# Clyde_main_board.net
KiCad netlist of a schematic drawn in EAGLE
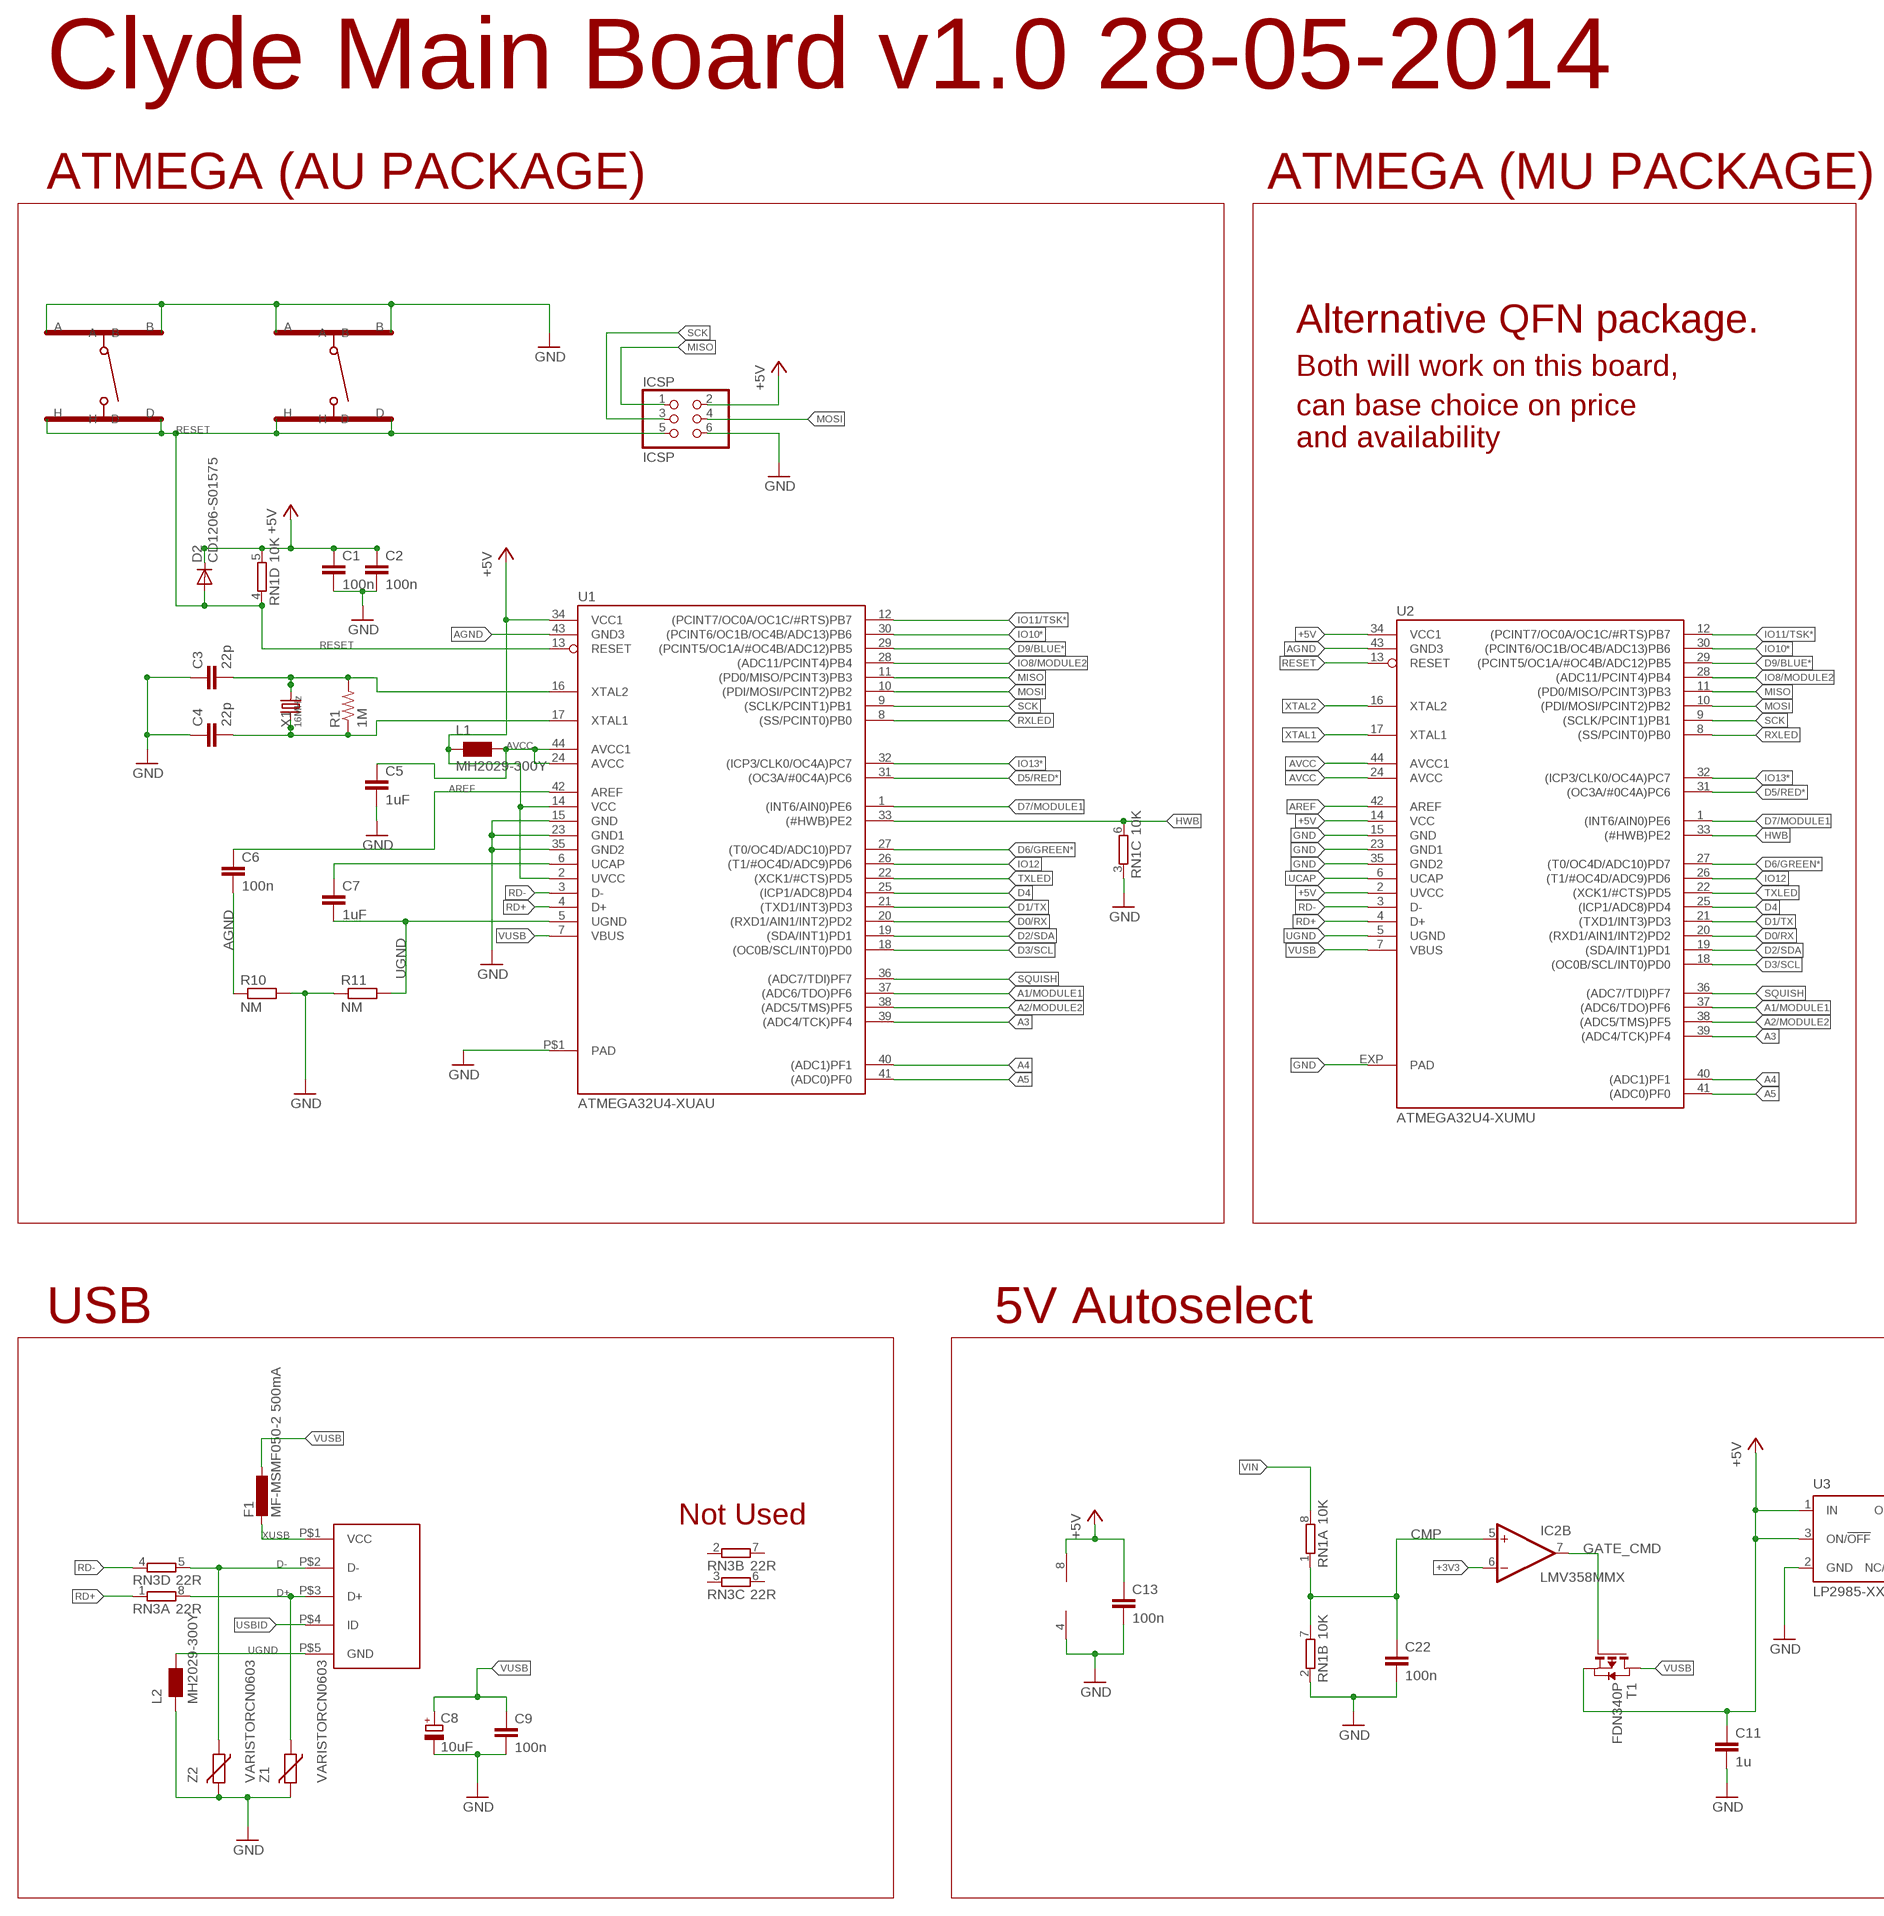
[diagram p0: schematic, sheet 1, part 1 of 2]
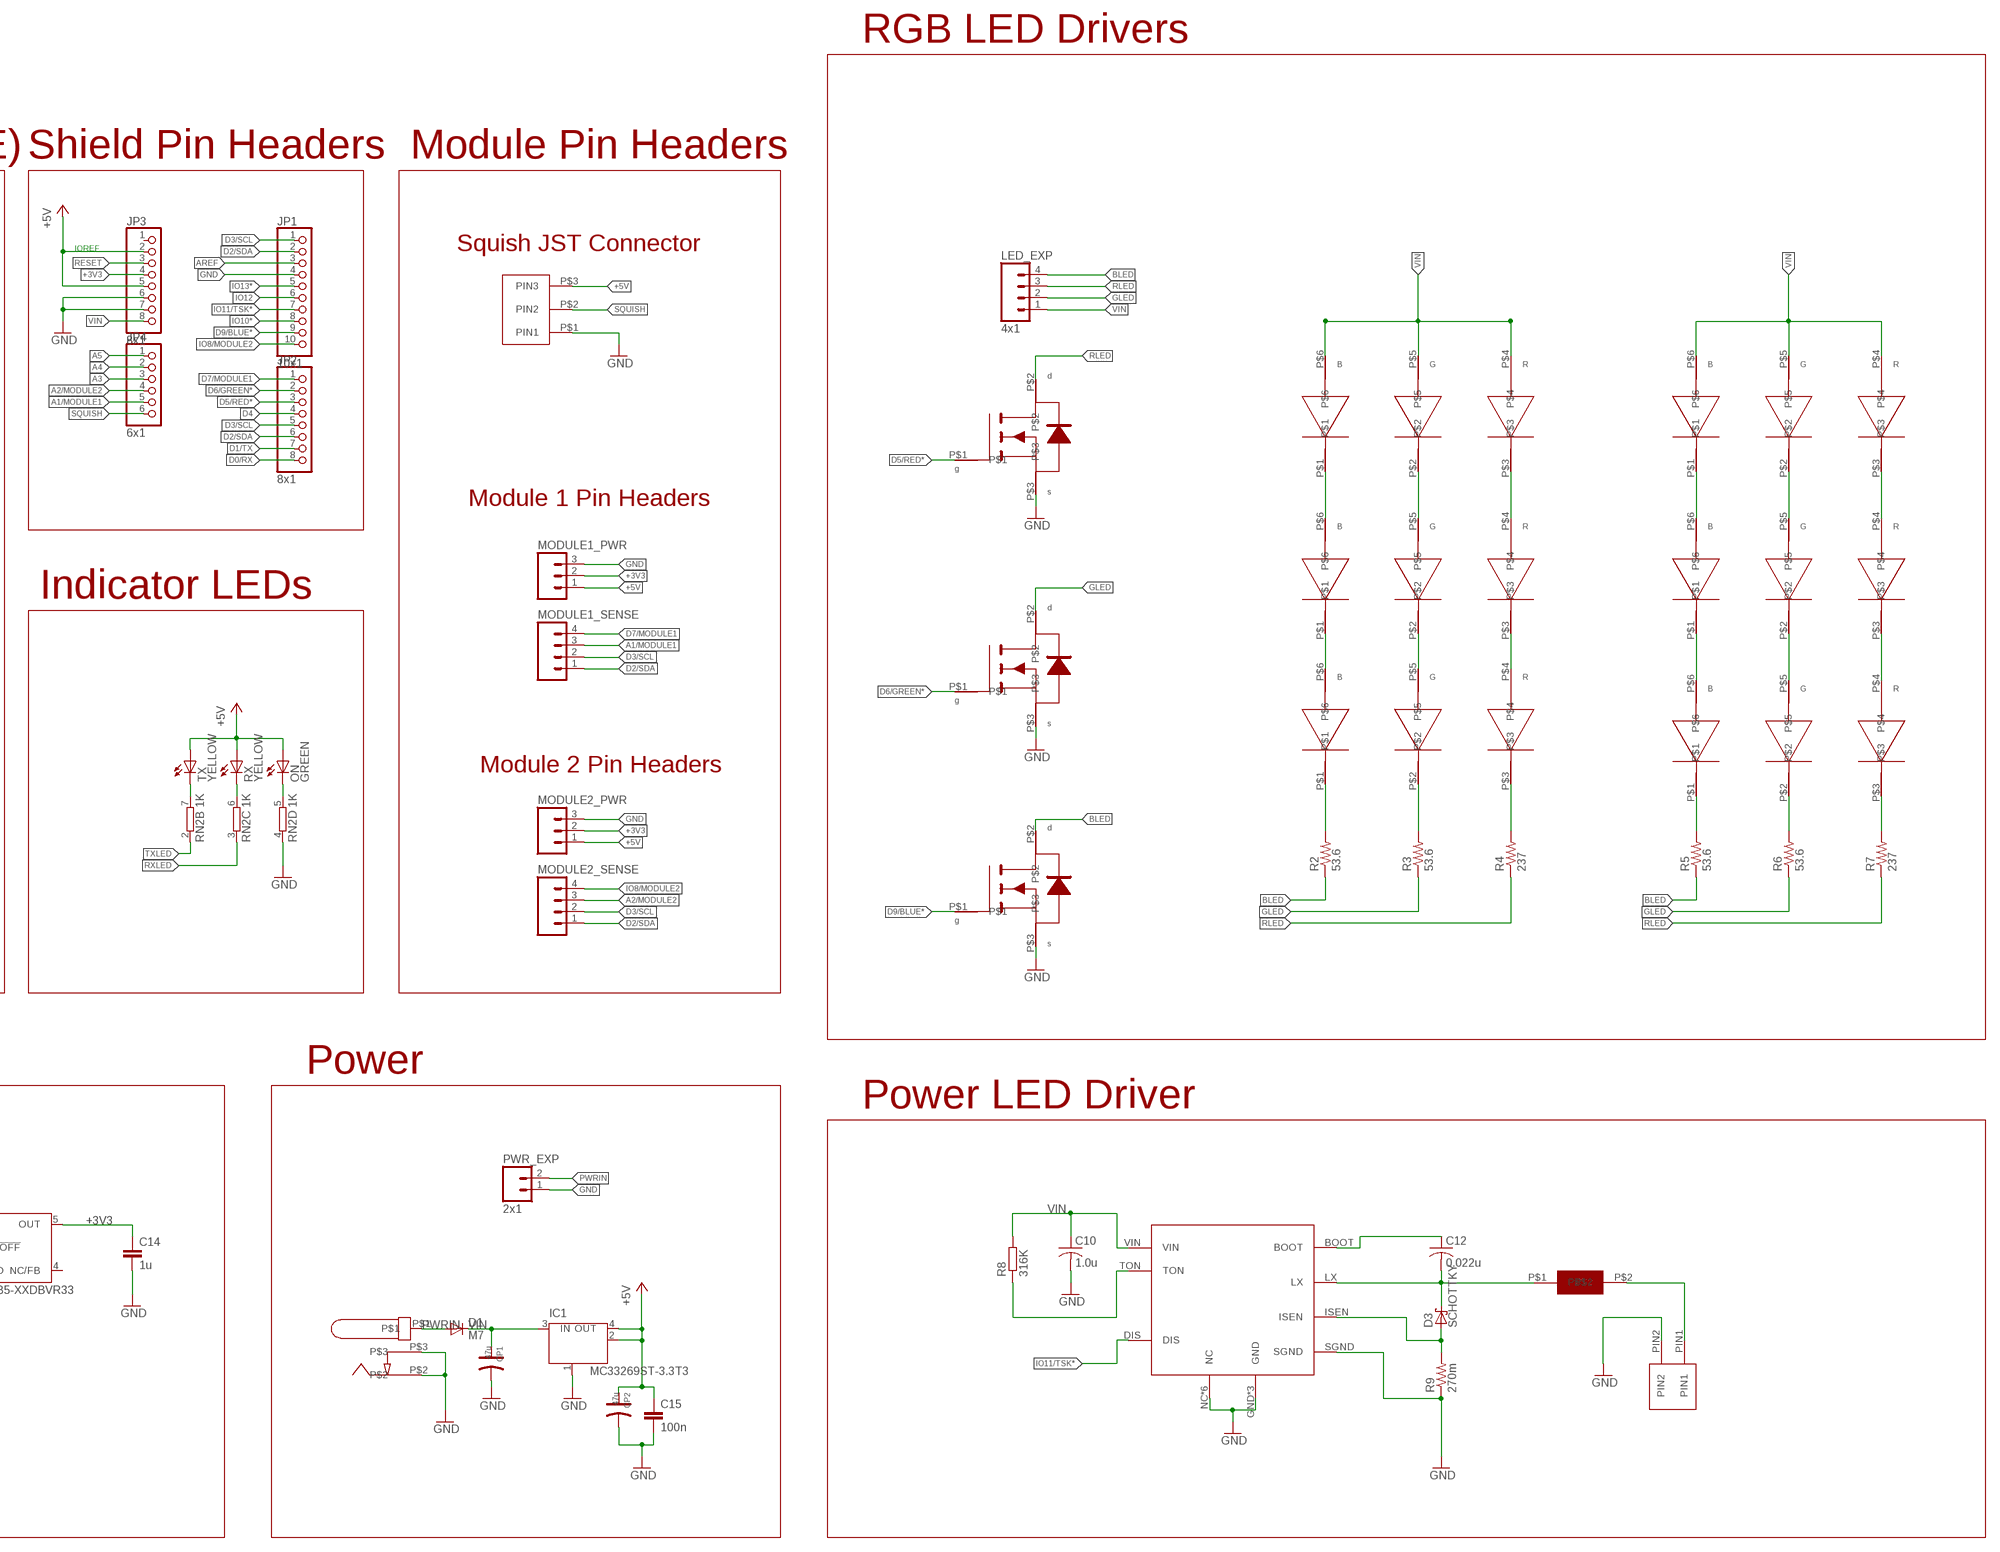
[diagram p1: schematic, sheet 1, part 2 of 2]

(export (version "E")
  (design (tool "Eeschema 10.0.6"))
  (components
    (comp (ref "2PIN_CONN")
      (value "XH_JST_CONN_2POS_TOP")
      (footprint "eagle-import:XH_JST_CONN_2POS_TOP")
      (libsource (lib "eagle-import") (part "XH_JST_CONN_2POS_TOP"))
    )
    (comp (ref "C1")
      (value "100n")
      (footprint "eagle-import:C0603-ROUND")
      (libsource (lib "eagle-import") (part "C-EUC0603"))
    )
    (comp (ref "C2")
      (value "100n")
      (footprint "eagle-import:C0603-ROUND")
      (libsource (lib "eagle-import") (part "C-EUC0603"))
    )
    (comp (ref "C3")
      (value "22p")
      (footprint "eagle-import:C0603-ROUND")
      (libsource (lib "eagle-import") (part "C-EUC0603"))
    )
    (comp (ref "C4")
      (value "22p")
      (footprint "eagle-import:C0603-ROUND")
      (libsource (lib "eagle-import") (part "C-EUC0603"))
    )
    (comp (ref "C5")
      (value "1uF")
      (footprint "eagle-import:C0603-ROUND")
      (libsource (lib "eagle-import") (part "C-EUC0603"))
    )
    (comp (ref "C6")
      (value "100n")
      (footprint "eagle-import:C0603-ROUND")
      (libsource (lib "eagle-import") (part "C-EUC0603"))
    )
    (comp (ref "C7")
      (value "1uF")
      (footprint "eagle-import:C0603-ROUND")
      (libsource (lib "eagle-import") (part "C-EUC0603"))
    )
    (comp (ref "C8")
      (value "10uF")
      (footprint "eagle-import:SMC_B")
      (libsource (lib "eagle-import") (part "CPOL-EUSMCB"))
    )
    (comp (ref "C9")
      (value "100n")
      (footprint "eagle-import:C0603-ROUND")
      (libsource (lib "eagle-import") (part "C-EUC0603"))
    )
    (comp (ref "C10")
      (value "1.0u")
      (footprint "eagle-import:C1210")
      (libsource (lib "eagle-import") (part "C-USC1210"))
    )
    (comp (ref "C11")
      (value "1u")
      (footprint "eagle-import:C0603-ROUND")
      (libsource (lib "eagle-import") (part "C-EUC0603"))
    )
    (comp (ref "C12")
      (value "0.022u")
      (footprint "eagle-import:C0805")
      (libsource (lib "eagle-import") (part "C-USC0805"))
    )
    (comp (ref "C13")
      (value "100n")
      (footprint "eagle-import:C0603-ROUND")
      (libsource (lib "eagle-import") (part "C-EUC0603"))
    )
    (comp (ref "C14")
      (value "1u")
      (footprint "eagle-import:C0603-ROUND")
      (libsource (lib "eagle-import") (part "C-EUC0603"))
    )
    (comp (ref "C15")
      (value "100n")
      (footprint "eagle-import:C0603-ROUND")
      (libsource (lib "eagle-import") (part "C-EUC0603"))
    )
    (comp (ref "C22")
      (value "100n")
      (footprint "eagle-import:C0603-ROUND")
      (libsource (lib "eagle-import") (part "C-EUC0603"))
    )
    (comp (ref "CP1")
      (value "47u")
      (footprint "eagle-import:ELECTRO-SMD-C-6MM")
      (libsource (lib "eagle-import") (part "CAP-ELECTRO-C"))
    )
    (comp (ref "CP2")
      (value "47u")
      (footprint "eagle-import:ELECTRO-SMD-C-6MM")
      (libsource (lib "eagle-import") (part "CAP-ELECTRO-C"))
    )
    (comp (ref "D1")
      (value "M7")
      (footprint "eagle-import:SMB")
      (libsource (lib "eagle-import") (part "DIODE-SMB"))
    )
    (comp (ref "D2")
      (value "CD1206-S01575")
      (footprint "eagle-import:MINIMELF")
      (libsource (lib "eagle-import") (part "DIODE-MINIMELF"))
    )
    (comp (ref "D3")
      (value "SCHOTTKY")
      (footprint "eagle-import:SMB")
      (libsource (lib "eagle-import") (part "SCHOTTKY-DIODESMD"))
    )
    (comp (ref "F1")
      (value "MF-MSMF050-2 500mA")
      (footprint "eagle-import:L1812")
      (libsource (lib "eagle-import") (part "L-EUL1812"))
    )
    (comp (ref "IC1")
      (value "MC33269ST-3.3T3")
      (footprint "eagle-import:SOT223")
      (libsource (lib "eagle-import") (part "MC33269ST-3.3T3"))
    )
    (comp (ref "IC2")
      (value "LMV358MMX")
      (footprint "eagle-import:MSOP08")
      (libsource (lib "eagle-import") (part "LMV358?MMX"))
    )
    (comp (ref "ICSP")
      (value "ICSP")
      (footprint "eagle-import:2X03")
      (libsource (lib "eagle-import") (part "PINHD-2X3"))
    )
    (comp (ref "IR_CONNECT")
      (value "XH_JST_CONN_3POS_SIDE_SMT")
      (footprint "eagle-import:XH_JST_CONN_3POS_SIDE_SMT")
      (libsource (lib "eagle-import") (part "XH_JST_CONN_3POS_SIDE_SMT"))
    )
    (comp (ref "I_LEDDRIVER")
      (value "TAIYO_YUDEN_6045_INDUCTOR")
      (footprint "eagle-import:TAIYO_YUDEN_6045_INDUCTOR")
      (libsource (lib "eagle-import") (part "TAIYO_YUDEN_6045_INDUCTOR"))
    )
    (comp (ref "J1")
      (value "MOLEX_VERT_MINIUSB")
      (footprint "eagle-import:MOLEX_VERT_MINIUSB")
      (libsource (lib "eagle-import") (part "MOLEX_VERT_MINIUSB"))
    )
    (comp (ref "JP1")
      (value "10x1")
      (footprint "eagle-import:1X10")
      (libsource (lib "eagle-import") (part "PINHD-1X10"))
    )
    (comp (ref "JP2")
      (value "8x1")
      (footprint "eagle-import:1X08")
      (libsource (lib "eagle-import") (part "PINHD-1X8"))
    )
    (comp (ref "JP3")
      (value "8x1")
      (footprint "eagle-import:1X08")
      (libsource (lib "eagle-import") (part "PINHD-1X8"))
    )
    (comp (ref "JP4")
      (value "6x1")
      (footprint "eagle-import:1X06")
      (libsource (lib "eagle-import") (part "PINHD-1X6"))
    )
    (comp (ref "L1")
      (value "MH2029-300Y")
      (footprint "eagle-import:0805")
      (libsource (lib "eagle-import") (part "WE-CBF_0805"))
    )
    (comp (ref "L2")
      (value "MH2029-300Y")
      (footprint "eagle-import:0805")
      (libsource (lib "eagle-import") (part "WE-CBF_0805"))
    )
    (comp (ref "LED_EXP")
      (value "4x1")
      (footprint "eagle-import:1X04_LONGPADS")
      (libsource (lib "eagle-import") (part "M04LONGPADS"))
    )
    (comp (ref "MODULE1_PWR")
      (value "M03PTH")
      (footprint "eagle-import:1X03")
      (libsource (lib "eagle-import") (part "M03PTH"))
    )
    (comp (ref "MODULE1_SENSE")
      (value "M04PTH")
      (footprint "eagle-import:1X04")
      (libsource (lib "eagle-import") (part "M04PTH"))
    )
    (comp (ref "MODULE2_PWR")
      (value "M03PTH")
      (footprint "eagle-import:1X03")
      (libsource (lib "eagle-import") (part "M03PTH"))
    )
    (comp (ref "MODULE2_SENSE")
      (value "M04PTH")
      (footprint "eagle-import:1X04")
      (libsource (lib "eagle-import") (part "M04PTH"))
    )
    (comp (ref "ON")
      (value "GREEN")
      (footprint "eagle-import:CHIPLED_0603")
      (libsource (lib "eagle-import") (part "LEDCHIPLED_0603"))
    )
    (comp (ref "PWR_EXP")
      (value "2x1")
      (footprint "eagle-import:SCREWTERMINAL-3.5MM-2")
      (libsource (lib "eagle-import") (part "M023.5MM"))
    )
    (comp (ref "PWR_JACK")
      (value "VERT_PWRJACK_PJ-006A_CUIINC")
      (footprint "eagle-import:VERT_PWRJACK_PJ-006A_CUIINC")
      (libsource (lib "eagle-import") (part "VERT_PWRJACK_PJ-006A_CUIINC"))
    )
    (comp (ref "R1")
      (value "1M")
      (footprint "eagle-import:0805")
      (libsource (lib "eagle-import") (part "RESISTOR0805-RES"))
    )
    (comp (ref "R2")
      (value "53.6")
      (footprint "eagle-import:R0603")
      (libsource (lib "eagle-import") (part "R-US_R0603"))
    )
    (comp (ref "R3")
      (value "53.6")
      (footprint "eagle-import:R0603")
      (libsource (lib "eagle-import") (part "R-US_R0603"))
    )
    (comp (ref "R4")
      (value "237")
      (footprint "eagle-import:R0603")
      (libsource (lib "eagle-import") (part "R-US_R0603"))
    )
    (comp (ref "R5")
      (value "53.6")
      (footprint "eagle-import:R0603")
      (libsource (lib "eagle-import") (part "R-US_R0603"))
    )
    (comp (ref "R6")
      (value "53.6")
      (footprint "eagle-import:R0603")
      (libsource (lib "eagle-import") (part "R-US_R0603"))
    )
    (comp (ref "R7")
      (value "237")
      (footprint "eagle-import:R0603")
      (libsource (lib "eagle-import") (part "R-US_R0603"))
    )
    (comp (ref "R8")
      (value "316K")
      (footprint "eagle-import:R0603-ROUND")
      (libsource (lib "eagle-import") (part "R-EU_R0603"))
    )
    (comp (ref "R9")
      (value "270m")
      (footprint "eagle-import:R0805")
      (libsource (lib "eagle-import") (part "resistor_R-US_R0805"))
    )
    (comp (ref "R10")
      (value "NM")
      (footprint "eagle-import:R0402_NM")
      (libsource (lib "eagle-import") (part "R_0402_NM"))
    )
    (comp (ref "R11")
      (value "NM")
      (footprint "eagle-import:R0402_NM")
      (libsource (lib "eagle-import") (part "R_0402_NM"))
    )
    (comp (ref "RGB1")
      (value "HANGZHOU_MULTICOLOR_3535WSA")
      (footprint "eagle-import:HANGZHOU_MULTCOLOR_3535WSZ")
      (libsource (lib "eagle-import") (part "HANGZHOU_MULTICOLOR_3535WSA"))
    )
    (comp (ref "RGB2")
      (value "HANGZHOU_MULTICOLOR_3535WSA")
      (footprint "eagle-import:HANGZHOU_MULTCOLOR_3535WSZ")
      (libsource (lib "eagle-import") (part "HANGZHOU_MULTICOLOR_3535WSA"))
    )
    (comp (ref "RGB3")
      (value "HANGZHOU_MULTICOLOR_3535WSA")
      (footprint "eagle-import:HANGZHOU_MULTCOLOR_3535WSZ")
      (libsource (lib "eagle-import") (part "HANGZHOU_MULTICOLOR_3535WSA"))
    )
    (comp (ref "RGB4")
      (value "HANGZHOU_MULTICOLOR_3535WSA")
      (footprint "eagle-import:HANGZHOU_MULTCOLOR_3535WSZ")
      (libsource (lib "eagle-import") (part "HANGZHOU_MULTICOLOR_3535WSA"))
    )
    (comp (ref "RGB5")
      (value "HANGZHOU_MULTICOLOR_3535WSA")
      (footprint "eagle-import:HANGZHOU_MULTCOLOR_3535WSZ")
      (libsource (lib "eagle-import") (part "HANGZHOU_MULTICOLOR_3535WSA"))
    )
    (comp (ref "RGB6")
      (value "HANGZHOU_MULTICOLOR_3535WSA")
      (footprint "eagle-import:HANGZHOU_MULTCOLOR_3535WSZ")
      (libsource (lib "eagle-import") (part "HANGZHOU_MULTICOLOR_3535WSA"))
    )
    (comp (ref "RN1")
      (value "10K")
      (footprint "eagle-import:CAY16")
      (libsource (lib "eagle-import") (part "4R-NCAY16"))
    )
    (comp (ref "RN2")
      (value "1K")
      (footprint "eagle-import:CAY16")
      (libsource (lib "eagle-import") (part "4R-NCAY16"))
    )
    (comp (ref "RN3")
      (value "22R")
      (footprint "eagle-import:CAY16")
      (libsource (lib "eagle-import") (part "4R-NCAY16"))
    )
    (comp (ref "RST")
      (value "COMAX_MINISWITCH")
      (footprint "eagle-import:COMAX_MINISWITCH")
      (libsource (lib "eagle-import") (part "COMAX_MINISWITCH"))
    )
    (comp (ref "RST1")
      (value "COMAX_MINISWITCH")
      (footprint "eagle-import:COMAX_MINISWITCH")
      (libsource (lib "eagle-import") (part "COMAX_MINISWITCH"))
    )
    (comp (ref "RX")
      (value "YELLOW")
      (footprint "eagle-import:CHIPLED_0603")
      (libsource (lib "eagle-import") (part "LEDCHIPLED_0603"))
    )
    (comp (ref "T1")
      (value "FDN340P")
      (footprint "eagle-import:SOT-23")
      (libsource (lib "eagle-import") (part "PMOSSOT23"))
    )
    (comp (ref "TBLUE")
      (value "SI2302DS_MOSFET")
      (footprint "eagle-import:SI2302DS_MOSFET")
      (libsource (lib "eagle-import") (part "SI2302DS_MOSFET"))
    )
    (comp (ref "TGREEN")
      (value "SI2302DS_MOSFET")
      (footprint "eagle-import:SI2302DS_MOSFET")
      (libsource (lib "eagle-import") (part "SI2302DS_MOSFET"))
    )
    (comp (ref "TRED")
      (value "SI2302DS_MOSFET")
      (footprint "eagle-import:SI2302DS_MOSFET")
      (libsource (lib "eagle-import") (part "SI2302DS_MOSFET"))
    )
    (comp (ref "TX")
      (value "YELLOW")
      (footprint "eagle-import:CHIPLED_0603")
      (libsource (lib "eagle-import") (part "LEDCHIPLED_0603"))
    )
    (comp (ref "U1")
      (value "ATMEGA32U4-XUAU")
      (footprint "eagle-import:TQFP44-PAD")
      (libsource (lib "eagle-import") (part "ATMEGA32U4-XUAU"))
    )
    (comp (ref "U2")
      (value "ATMEGA32U4-XUMU")
      (footprint "eagle-import:QFN44ML7X7")
      (libsource (lib "eagle-import") (part "ATMEGA32U4-XUMU"))
    )
    (comp (ref "U3")
      (value "LP2985-XXDBVR33")
      (footprint "eagle-import:SOT23-DBV")
      (libsource (lib "eagle-import") (part "LP2985-XXDBVR33"))
    )
    (comp (ref "U4")
      (value "ALLEGRO_A6210")
      (footprint "eagle-import:ALLEGRO_A6210")
      (libsource (lib "eagle-import") (part "ALLEGRO_A6210"))
    )
    (comp (ref "X1")
      (value "16MHz")
      (footprint "eagle-import:XTAL_THRU_SMT")
      (libsource (lib "eagle-import") (part "XTAL_THRU_SMD"))
    )
    (comp (ref "Z1")
      (value "VARISTORCN0603")
      (footprint "eagle-import:CT_CN0603")
      (libsource (lib "eagle-import") (part "VARISTORCN0603"))
    )
    (comp (ref "Z2")
      (value "VARISTORCN0603")
      (footprint "eagle-import:CT_CN0603")
      (libsource (lib "eagle-import") (part "VARISTORCN0603"))
    )
  )
  (nets
    (net (code "1") (name "+3V3") (class "Default")
      (node (ref "C14") (pin "1") (pinfunction "1_1") (pintype "passive"))
      (node (ref "IC2") (pin "6") (pinfunction "-IN_6") (pintype "input"))
      (node (ref "JP3") (pin "4") (pinfunction "4_4") (pintype "passive"))
      (node (ref "MODULE1_PWR") (pin "2") (pinfunction "2_2") (pintype "passive"))
      (node (ref "MODULE2_PWR") (pin "2") (pinfunction "2_2") (pintype "passive"))
      (node (ref "U3") (pin "5") (pinfunction "OUT_5") (pintype "passive"))
    )
    (net (code "2") (name "+5V") (class "Default")
      (node (ref "C1") (pin "1") (pinfunction "1_1") (pintype "passive"))
      (node (ref "C11") (pin "1") (pinfunction "1_1") (pintype "passive"))
      (node (ref "C13") (pin "1") (pinfunction "1_1") (pintype "passive"))
      (node (ref "C15") (pin "1") (pinfunction "1_1") (pintype "passive"))
      (node (ref "C2") (pin "1") (pinfunction "1_1") (pintype "passive"))
      (node (ref "CP2") (pin "+") (pinfunction "+_+") (pintype "passive"))
      (node (ref "D2") (pin "C") (pinfunction "C_C") (pintype "passive"))
      (node (ref "IC1") (pin "2") (pinfunction "OUT_2") (pintype "passive"))
      (node (ref "IC1") (pin "4") (pinfunction "OUT_4") (pintype "passive"))
      (node (ref "IC2") (pin "8") (pinfunction "V+_8") (pintype "power_in"))
      (node (ref "ICSP") (pin "2") (pinfunction "2_2") (pintype "passive"))
      (node (ref "IR_CONNECT") (pin "P$3") (pinfunction "PIN3_P$3") (pintype "bidirectional"))
      (node (ref "JP3") (pin "2") (pinfunction "2_2") (pintype "passive"))
      (node (ref "JP3") (pin "5") (pinfunction "5_5") (pintype "passive"))
      (node (ref "L1") (pin "1") (pinfunction "1_1") (pintype "passive"))
      (node (ref "MODULE1_PWR") (pin "1") (pinfunction "1_1") (pintype "passive"))
      (node (ref "MODULE2_PWR") (pin "1") (pinfunction "1_1") (pintype "passive"))
      (node (ref "ON") (pin "A") (pinfunction "A_A") (pintype "passive"))
      (node (ref "RN1") (pin "5") (pinfunction "2_5") (pintype "passive"))
      (node (ref "RX") (pin "A") (pinfunction "A_A") (pintype "passive"))
      (node (ref "T1") (pin "2") (pinfunction "S_2") (pintype "passive"))
      (node (ref "TX") (pin "A") (pinfunction "A_A") (pintype "passive"))
      (node (ref "U1") (pin "14") (pinfunction "VCC_14") (pintype "power_in"))
      (node (ref "U1") (pin "2") (pinfunction "UVCC_2") (pintype "power_in"))
      (node (ref "U1") (pin "34") (pinfunction "VCC1_34") (pintype "power_in"))
      (node (ref "U2") (pin "14") (pinfunction "VCC_14") (pintype "power_in"))
      (node (ref "U2") (pin "2") (pinfunction "UVCC_2") (pintype "power_in"))
      (node (ref "U2") (pin "34") (pinfunction "VCC1_34") (pintype "power_in"))
      (node (ref "U3") (pin "1") (pinfunction "IN_1") (pintype "input"))
      (node (ref "U3") (pin "3") (pinfunction "ON/~{OFF}_3") (pintype "input"))
    )
    (net (code "3") (name "/CMP") (class "Default")
      (node (ref "C22") (pin "1") (pinfunction "1_1") (pintype "passive"))
      (node (ref "IC2") (pin "5") (pinfunction "+IN_5") (pintype "input"))
      (node (ref "RN1") (pin "1") (pinfunction "1_1") (pintype "passive"))
      (node (ref "RN1") (pin "7") (pinfunction "2_7") (pintype "passive"))
    )
    (net (code "4") (name "/D+") (class "Default")
      (node (ref "J1") (pin "P$3") (pinfunction "D+_P$3") (pintype "bidirectional"))
      (node (ref "RN3") (pin "8") (pinfunction "2_8") (pintype "passive"))
      (node (ref "Z1") (pin "1") (pinfunction "1_1") (pintype "passive"))
    )
    (net (code "5") (name "/D-") (class "Default")
      (node (ref "J1") (pin "P$2") (pinfunction "D-_P$2") (pintype "bidirectional"))
      (node (ref "RN3") (pin "5") (pinfunction "2_5") (pintype "passive"))
      (node (ref "Z2") (pin "1") (pinfunction "1_1") (pintype "passive"))
    )
    (net (code "6") (name "/GATE_CMD") (class "Default")
      (node (ref "IC2") (pin "7") (pinfunction "OUT_7") (pintype "output"))
      (node (ref "T1") (pin "3") (pinfunction "G_3") (pintype "passive"))
    )
    (net (code "7") (name "/XUSB") (class "Default")
      (node (ref "F1") (pin "2") (pinfunction "2_2") (pintype "passive"))
      (node (ref "J1") (pin "P$1") (pinfunction "VCC_P$1") (pintype "bidirectional"))
    )
    (net (code "8") (name "A1{slash}MODULE1") (class "Default")
      (node (ref "JP4") (pin "5") (pinfunction "5_5") (pintype "passive"))
      (node (ref "MODULE1_SENSE") (pin "3") (pinfunction "3_3") (pintype "passive"))
      (node (ref "U1") (pin "37") (pinfunction "(ADC6/TDO)PF6_37") (pintype "bidirectional"))
      (node (ref "U2") (pin "37") (pinfunction "(ADC6/TDO)PF6_37") (pintype "bidirectional"))
    )
    (net (code "9") (name "A2{slash}MODULE2") (class "Default")
      (node (ref "JP4") (pin "4") (pinfunction "4_4") (pintype "passive"))
      (node (ref "MODULE2_SENSE") (pin "3") (pinfunction "3_3") (pintype "passive"))
      (node (ref "U1") (pin "38") (pinfunction "(ADC5/TMS)PF5_38") (pintype "bidirectional"))
      (node (ref "U2") (pin "38") (pinfunction "(ADC5/TMS)PF5_38") (pintype "bidirectional"))
    )
    (net (code "10") (name "A3") (class "Default")
      (node (ref "JP4") (pin "3") (pinfunction "3_3") (pintype "passive"))
      (node (ref "U1") (pin "39") (pinfunction "(ADC4/TCK)PF4_39") (pintype "bidirectional"))
      (node (ref "U2") (pin "39") (pinfunction "(ADC4/TCK)PF4_39") (pintype "bidirectional"))
    )
    (net (code "11") (name "A4") (class "Default")
      (node (ref "JP4") (pin "2") (pinfunction "2_2") (pintype "passive"))
      (node (ref "U1") (pin "40") (pinfunction "(ADC1)PF1_40") (pintype "bidirectional"))
      (node (ref "U2") (pin "40") (pinfunction "(ADC1)PF1_40") (pintype "bidirectional"))
    )
    (net (code "12") (name "A5") (class "Default")
      (node (ref "JP4") (pin "1") (pinfunction "1_1") (pintype "passive"))
      (node (ref "U1") (pin "41") (pinfunction "(ADC0)PF0_41") (pintype "bidirectional"))
      (node (ref "U2") (pin "41") (pinfunction "(ADC0)PF0_41") (pintype "bidirectional"))
    )
    (net (code "13") (name "AGND") (class "Default")
      (node (ref "C6") (pin "2") (pinfunction "2_2") (pintype "passive"))
      (node (ref "R10") (pin "1") (pinfunction "1_1") (pintype "passive"))
      (node (ref "U1") (pin "43") (pinfunction "GND3_43") (pintype "power_in"))
      (node (ref "U2") (pin "43") (pinfunction "GND3_43") (pintype "power_in"))
    )
    (net (code "14") (name "AREF") (class "Default")
      (node (ref "C6") (pin "1") (pinfunction "1_1") (pintype "passive"))
      (node (ref "JP1") (pin "3") (pinfunction "3_3") (pintype "passive"))
      (node (ref "U1") (pin "42") (pinfunction "AREF_42") (pintype "power_in"))
      (node (ref "U2") (pin "42") (pinfunction "AREF_42") (pintype "power_in"))
    )
    (net (code "15") (name "AVCC") (class "Default")
      (node (ref "C5") (pin "1") (pinfunction "1_1") (pintype "passive"))
      (node (ref "L1") (pin "2") (pinfunction "2_2") (pintype "passive"))
      (node (ref "U1") (pin "24") (pinfunction "AVCC_24") (pintype "power_in"))
      (node (ref "U1") (pin "44") (pinfunction "AVCC1_44") (pintype "power_in"))
      (node (ref "U2") (pin "24") (pinfunction "AVCC_24") (pintype "power_in"))
      (node (ref "U2") (pin "44") (pinfunction "AVCC1_44") (pintype "power_in"))
    )
    (net (code "16") (name "BLED") (class "Default")
      (node (ref "LED_EXP") (pin "4") (pinfunction "4_4") (pintype "passive"))
      (node (ref "R2") (pin "1") (pinfunction "1_1") (pintype "passive"))
      (node (ref "R5") (pin "1") (pinfunction "1_1") (pintype "passive"))
      (node (ref "TBLUE") (pin "P$2") (pinfunction "P$2_P$2") (pintype "bidirectional"))
    )
    (net (code "17") (name "D0{slash}RX") (class "Default")
      (node (ref "JP2") (pin "8") (pinfunction "8_8") (pintype "passive"))
      (node (ref "U1") (pin "20") (pinfunction "(RXD1/AIN1/INT2)PD2_20") (pintype "bidirectional"))
      (node (ref "U2") (pin "20") (pinfunction "(RXD1/AIN1/INT2)PD2_20") (pintype "bidirectional"))
    )
    (net (code "18") (name "D1{slash}TX") (class "Default")
      (node (ref "JP2") (pin "7") (pinfunction "7_7") (pintype "passive"))
      (node (ref "U1") (pin "21") (pinfunction "(TXD1/INT3)PD3_21") (pintype "bidirectional"))
      (node (ref "U2") (pin "21") (pinfunction "(TXD1/INT3)PD3_21") (pintype "bidirectional"))
    )
    (net (code "19") (name "D2{slash}SDA") (class "Default")
      (node (ref "JP1") (pin "2") (pinfunction "2_2") (pintype "passive"))
      (node (ref "JP2") (pin "6") (pinfunction "6_6") (pintype "passive"))
      (node (ref "MODULE1_SENSE") (pin "1") (pinfunction "1_1") (pintype "passive"))
      (node (ref "MODULE2_SENSE") (pin "1") (pinfunction "1_1") (pintype "passive"))
      (node (ref "U1") (pin "19") (pinfunction "(SDA/INT1)PD1_19") (pintype "bidirectional"))
      (node (ref "U2") (pin "19") (pinfunction "(SDA/INT1)PD1_19") (pintype "bidirectional"))
    )
    (net (code "20") (name "D3{slash}SCL") (class "Default")
      (node (ref "JP1") (pin "1") (pinfunction "1_1") (pintype "passive"))
      (node (ref "JP2") (pin "5") (pinfunction "5_5") (pintype "passive"))
      (node (ref "MODULE1_SENSE") (pin "2") (pinfunction "2_2") (pintype "passive"))
      (node (ref "MODULE2_SENSE") (pin "2") (pinfunction "2_2") (pintype "passive"))
      (node (ref "U1") (pin "18") (pinfunction "(OC0B/SCL/INT0)PD0_18") (pintype "bidirectional"))
      (node (ref "U2") (pin "18") (pinfunction "(OC0B/SCL/INT0)PD0_18") (pintype "bidirectional"))
    )
    (net (code "21") (name "D4") (class "Default")
      (node (ref "JP2") (pin "4") (pinfunction "4_4") (pintype "passive"))
      (node (ref "U1") (pin "25") (pinfunction "(ICP1/ADC8)PD4_25") (pintype "bidirectional"))
      (node (ref "U2") (pin "25") (pinfunction "(ICP1/ADC8)PD4_25") (pintype "bidirectional"))
    )
    (net (code "22") (name "D5{slash}RED*") (class "Default")
      (node (ref "JP2") (pin "3") (pinfunction "3_3") (pintype "passive"))
      (node (ref "TRED") (pin "P$1") (pinfunction "P$1_P$1") (pintype "bidirectional"))
      (node (ref "U1") (pin "31") (pinfunction "(OC3A/#0C4A)PC6_31") (pintype "bidirectional"))
      (node (ref "U2") (pin "31") (pinfunction "(OC3A/#0C4A)PC6_31") (pintype "bidirectional"))
    )
    (net (code "23") (name "D6{slash}GREEN*") (class "Default")
      (node (ref "JP2") (pin "2") (pinfunction "2_2") (pintype "passive"))
      (node (ref "TGREEN") (pin "P$1") (pinfunction "P$1_P$1") (pintype "bidirectional"))
      (node (ref "U1") (pin "27") (pinfunction "(T0/OC4D/ADC10)PD7_27") (pintype "bidirectional"))
      (node (ref "U2") (pin "27") (pinfunction "(T0/OC4D/ADC10)PD7_27") (pintype "bidirectional"))
    )
    (net (code "24") (name "D7{slash}MODULE1") (class "Default")
      (node (ref "JP2") (pin "1") (pinfunction "1_1") (pintype "passive"))
      (node (ref "MODULE1_SENSE") (pin "4") (pinfunction "4_4") (pintype "passive"))
      (node (ref "U1") (pin "1") (pinfunction "(INT6/AIN0)PE6_1") (pintype "bidirectional"))
      (node (ref "U2") (pin "1") (pinfunction "(INT6/AIN0)PE6_1") (pintype "bidirectional"))
    )
    (net (code "25") (name "D9{slash}BLUE*") (class "Default")
      (node (ref "JP1") (pin "9") (pinfunction "9_9") (pintype "passive"))
      (node (ref "TBLUE") (pin "P$1") (pinfunction "P$1_P$1") (pintype "bidirectional"))
      (node (ref "U1") (pin "29") (pinfunction "(PCINT5/OC1A/#OC4B/ADC12)PB5_29") (pintype "bidirectional"))
      (node (ref "U2") (pin "29") (pinfunction "(PCINT5/OC1A/#OC4B/ADC12)PB5_29") (pintype "bidirectional"))
    )
    (net (code "26") (name "GLED") (class "Default")
      (node (ref "LED_EXP") (pin "2") (pinfunction "2_2") (pintype "passive"))
      (node (ref "R3") (pin "1") (pinfunction "1_1") (pintype "passive"))
      (node (ref "R6") (pin "1") (pinfunction "1_1") (pintype "passive"))
      (node (ref "TGREEN") (pin "P$2") (pinfunction "P$2_P$2") (pintype "bidirectional"))
    )
    (net (code "27") (name "GND") (class "Default")
      (node (ref "2PIN_CONN") (pin "PIN2") (pinfunction "PIN2_PIN2") (pintype "bidirectional"))
      (node (ref "C1") (pin "2") (pinfunction "2_2") (pintype "passive"))
      (node (ref "C10") (pin "2") (pinfunction "2_2") (pintype "passive"))
      (node (ref "C11") (pin "2") (pinfunction "2_2") (pintype "passive"))
      (node (ref "C13") (pin "2") (pinfunction "2_2") (pintype "passive"))
      (node (ref "C14") (pin "2") (pinfunction "2_2") (pintype "passive"))
      (node (ref "C15") (pin "2") (pinfunction "2_2") (pintype "passive"))
      (node (ref "C2") (pin "2") (pinfunction "2_2") (pintype "passive"))
      (node (ref "C22") (pin "2") (pinfunction "2_2") (pintype "passive"))
      (node (ref "C3") (pin "1") (pinfunction "1_1") (pintype "passive"))
      (node (ref "C4") (pin "1") (pinfunction "1_1") (pintype "passive"))
      (node (ref "C5") (pin "2") (pinfunction "2_2") (pintype "passive"))
      (node (ref "C8") (pin "-") (pinfunction "-_-") (pintype "passive"))
      (node (ref "C9") (pin "2") (pinfunction "2_2") (pintype "passive"))
      (node (ref "CP1") (pin "-") (pinfunction "-_-") (pintype "passive"))
      (node (ref "CP2") (pin "-") (pinfunction "-_-") (pintype "passive"))
      (node (ref "IC1") (pin "1") (pinfunction "GND/ADJ_1") (pintype "input"))
      (node (ref "IC2") (pin "4") (pinfunction "V-_4") (pintype "power_in"))
      (node (ref "ICSP") (pin "6") (pinfunction "6_6") (pintype "passive"))
      (node (ref "IR_CONNECT") (pin "P$1") (pinfunction "PIN1_P$1") (pintype "bidirectional"))
      (node (ref "JP1") (pin "4") (pinfunction "4_4") (pintype "passive"))
      (node (ref "JP3") (pin "6") (pinfunction "6_6") (pintype "passive"))
      (node (ref "JP3") (pin "7") (pinfunction "7_7") (pintype "passive"))
      (node (ref "L2") (pin "1") (pinfunction "1_1") (pintype "passive"))
      (node (ref "MODULE1_PWR") (pin "3") (pinfunction "3_3") (pintype "passive"))
      (node (ref "MODULE2_PWR") (pin "3") (pinfunction "3_3") (pintype "passive"))
      (node (ref "PWR_EXP") (pin "1") (pinfunction "1_1") (pintype "passive"))
      (node (ref "PWR_JACK") (pin "P$2") (pinfunction "P$2_P$2") (pintype "bidirectional"))
      (node (ref "PWR_JACK") (pin "P$3") (pinfunction "P$3_P$3") (pintype "bidirectional"))
      (node (ref "R10") (pin "2") (pinfunction "2_2") (pintype "passive"))
      (node (ref "R11") (pin "1") (pinfunction "1_1") (pintype "passive"))
      (node (ref "R9") (pin "1") (pinfunction "1_1") (pintype "passive"))
      (node (ref "RN1") (pin "2") (pinfunction "1_2") (pintype "passive"))
      (node (ref "RN1") (pin "3") (pinfunction "1_3") (pintype "passive"))
      (node (ref "RN2") (pin "4") (pinfunction "1_4") (pintype "passive"))
      (node (ref "RST") (pin "A") (pinfunction "A_A") (pintype "bidirectional"))
      (node (ref "RST") (pin "B") (pinfunction "B_B") (pintype "bidirectional"))
      (node (ref "RST1") (pin "A") (pinfunction "A_A") (pintype "bidirectional"))
      (node (ref "RST1") (pin "B") (pinfunction "B_B") (pintype "bidirectional"))
      (node (ref "TBLUE") (pin "P$3") (pinfunction "P$3_P$3") (pintype "bidirectional"))
      (node (ref "TGREEN") (pin "P$3") (pinfunction "P$3_P$3") (pintype "bidirectional"))
      (node (ref "TRED") (pin "P$3") (pinfunction "P$3_P$3") (pintype "bidirectional"))
      (node (ref "U1") (pin "15") (pinfunction "GND_15") (pintype "power_in"))
      (node (ref "U1") (pin "23") (pinfunction "GND1_23") (pintype "power_in"))
      (node (ref "U1") (pin "35") (pinfunction "GND2_35") (pintype "power_in"))
      (node (ref "U1") (pin "P$1") (pinfunction "PAD_P$1") (pintype "power_in"))
      (node (ref "U2") (pin "15") (pinfunction "GND_15") (pintype "power_in"))
      (node (ref "U2") (pin "23") (pinfunction "GND1_23") (pintype "power_in"))
      (node (ref "U2") (pin "35") (pinfunction "GND2_35") (pintype "power_in"))
      (node (ref "U2") (pin "EXP") (pinfunction "PAD_EXP") (pintype "power_in"))
      (node (ref "U3") (pin "2") (pinfunction "GND_2") (pintype "power_in"))
      (node (ref "U4") (pin "GND") (pinfunction "GND_GND") (pintype "bidirectional"))
      (node (ref "U4") (pin "GND1") (pinfunction "GND_GND1") (pintype "bidirectional"))
      (node (ref "U4") (pin "GND2") (pinfunction "GND_GND2") (pintype "bidirectional"))
      (node (ref "U4") (pin "NC") (pinfunction "NC_NC") (pintype "bidirectional"))
      (node (ref "U4") (pin "NC1") (pinfunction "NC_NC1") (pintype "bidirectional"))
      (node (ref "U4") (pin "NC2") (pinfunction "NC_NC2") (pintype "bidirectional"))
      (node (ref "U4") (pin "NC3") (pinfunction "NC_NC3") (pintype "bidirectional"))
      (node (ref "U4") (pin "NC4") (pinfunction "NC_NC4") (pintype "bidirectional"))
      (node (ref "U4") (pin "NC5") (pinfunction "NC_NC5") (pintype "bidirectional"))
      (node (ref "U4") (pin "SGND") (pinfunction "SGND_SGND") (pintype "bidirectional"))
      (node (ref "Z1") (pin "2") (pinfunction "2_2") (pintype "passive"))
      (node (ref "Z2") (pin "2") (pinfunction "2_2") (pintype "passive"))
    )
    (net (code "28") (name "HWB") (class "Default")
      (node (ref "RN1") (pin "6") (pinfunction "2_6") (pintype "passive"))
      (node (ref "U1") (pin "33") (pinfunction "(#HWB)PE2_33") (pintype "bidirectional"))
      (node (ref "U2") (pin "33") (pinfunction "(#HWB)PE2_33") (pintype "bidirectional"))
    )
    (net (code "29") (name "IO8{slash}MODULE2") (class "Default")
      (node (ref "JP1") (pin "10") (pinfunction "10_10") (pintype "passive"))
      (node (ref "MODULE2_SENSE") (pin "4") (pinfunction "4_4") (pintype "passive"))
      (node (ref "U1") (pin "28") (pinfunction "(ADC11/PCINT4)PB4_28") (pintype "bidirectional"))
      (node (ref "U2") (pin "28") (pinfunction "(ADC11/PCINT4)PB4_28") (pintype "bidirectional"))
    )
    (net (code "30") (name "IO10*") (class "Default")
      (node (ref "JP1") (pin "8") (pinfunction "8_8") (pintype "passive"))
      (node (ref "U1") (pin "30") (pinfunction "(PCINT6/OC1B/OC4B/ADC13)PB6_30") (pintype "bidirectional"))
      (node (ref "U2") (pin "30") (pinfunction "(PCINT6/OC1B/OC4B/ADC13)PB6_30") (pintype "bidirectional"))
    )
    (net (code "31") (name "IO11{slash}TSK*") (class "Default")
      (node (ref "JP1") (pin "7") (pinfunction "7_7") (pintype "passive"))
      (node (ref "U1") (pin "12") (pinfunction "(PCINT7/OC0A/OC1C/#RTS)PB7_12") (pintype "bidirectional"))
      (node (ref "U2") (pin "12") (pinfunction "(PCINT7/OC0A/OC1C/#RTS)PB7_12") (pintype "bidirectional"))
      (node (ref "U4") (pin "DIS") (pinfunction "DIS_DIS") (pintype "bidirectional"))
    )
    (net (code "32") (name "IO12") (class "Default")
      (node (ref "JP1") (pin "6") (pinfunction "6_6") (pintype "passive"))
      (node (ref "U1") (pin "26") (pinfunction "(T1/#OC4D/ADC9)PD6_26") (pintype "bidirectional"))
      (node (ref "U2") (pin "26") (pinfunction "(T1/#OC4D/ADC9)PD6_26") (pintype "bidirectional"))
    )
    (net (code "33") (name "IO13*") (class "Default")
      (node (ref "JP1") (pin "5") (pinfunction "5_5") (pintype "passive"))
      (node (ref "U1") (pin "32") (pinfunction "(ICP3/CLK0/OC4A)PC7_32") (pintype "bidirectional"))
      (node (ref "U2") (pin "32") (pinfunction "(ICP3/CLK0/OC4A)PC7_32") (pintype "bidirectional"))
    )
    (net (code "34") (name "MISO") (class "Default")
      (node (ref "ICSP") (pin "1") (pinfunction "1_1") (pintype "passive"))
      (node (ref "U1") (pin "11") (pinfunction "(PD0/MISO/PCINT3)PB3_11") (pintype "bidirectional"))
      (node (ref "U2") (pin "11") (pinfunction "(PD0/MISO/PCINT3)PB3_11") (pintype "bidirectional"))
    )
    (net (code "35") (name "MOSI") (class "Default")
      (node (ref "ICSP") (pin "4") (pinfunction "4_4") (pintype "passive"))
      (node (ref "U1") (pin "10") (pinfunction "(PDI/MOSI/PCINT2)PB2_10") (pintype "bidirectional"))
      (node (ref "U2") (pin "10") (pinfunction "(PDI/MOSI/PCINT2)PB2_10") (pintype "bidirectional"))
    )
    (net (code "36") (name "Net-(2PIN_CONN-PadPIN1)") (class "Default")
      (node (ref "2PIN_CONN") (pin "PIN1") (pinfunction "PIN1_PIN1") (pintype "bidirectional"))
      (node (ref "I_LEDDRIVER") (pin "P$2") (pinfunction "P$2_P$2") (pintype "bidirectional"))
    )
    (net (code "37") (name "Net-(C12-Pad1)") (class "Default")
      (node (ref "C12") (pin "1") (pinfunction "1_1") (pintype "passive"))
      (node (ref "U4") (pin "BOOT") (pinfunction "BOOT_BOOT") (pintype "bidirectional"))
    )
    (net (code "38") (name "Net-(C12-Pad2)") (class "Default")
      (node (ref "C12") (pin "2") (pinfunction "2_2") (pintype "passive"))
      (node (ref "D3") (pin "C") (pinfunction "C_C") (pintype "passive"))
      (node (ref "I_LEDDRIVER") (pin "P$1") (pinfunction "P$1_P$1") (pintype "bidirectional"))
      (node (ref "U4") (pin "LX") (pinfunction "LX_LX") (pintype "bidirectional"))
    )
    (net (code "39") (name "Net-(D3-PadA)") (class "Default")
      (node (ref "D3") (pin "A") (pinfunction "A_A") (pintype "passive"))
      (node (ref "R9") (pin "2") (pinfunction "2_2") (pintype "passive"))
      (node (ref "U4") (pin "ISEN") (pinfunction "ISEN_ISEN") (pintype "bidirectional"))
    )
    (net (code "40") (name "Net-(R2-Pad2)") (class "Default")
      (node (ref "R2") (pin "2") (pinfunction "2_2") (pintype "passive"))
      (node (ref "RGB3") (pin "P$1") (pinfunction "P$1_P$1") (pintype "bidirectional"))
    )
    (net (code "41") (name "Net-(R3-Pad2)") (class "Default")
      (node (ref "R3") (pin "2") (pinfunction "2_2") (pintype "passive"))
      (node (ref "RGB3") (pin "P$2") (pinfunction "P$2_P$2") (pintype "bidirectional"))
    )
    (net (code "42") (name "Net-(R4-Pad2)") (class "Default")
      (node (ref "R4") (pin "2") (pinfunction "2_2") (pintype "passive"))
      (node (ref "RGB3") (pin "P$3") (pinfunction "P$3_P$3") (pintype "bidirectional"))
    )
    (net (code "43") (name "Net-(R5-Pad2)") (class "Default")
      (node (ref "R5") (pin "2") (pinfunction "2_2") (pintype "passive"))
      (node (ref "RGB6") (pin "P$1") (pinfunction "P$1_P$1") (pintype "bidirectional"))
    )
    (net (code "44") (name "Net-(R6-Pad2)") (class "Default")
      (node (ref "R6") (pin "2") (pinfunction "2_2") (pintype "passive"))
      (node (ref "RGB6") (pin "P$2") (pinfunction "P$2_P$2") (pintype "bidirectional"))
    )
    (net (code "45") (name "Net-(R7-Pad2)") (class "Default")
      (node (ref "R7") (pin "2") (pinfunction "2_2") (pintype "passive"))
      (node (ref "RGB6") (pin "P$3") (pinfunction "P$3_P$3") (pintype "bidirectional"))
    )
    (net (code "46") (name "Net-(R8-Pad1)") (class "Default")
      (node (ref "R8") (pin "1") (pinfunction "1_1") (pintype "passive"))
      (node (ref "U4") (pin "TON") (pinfunction "TON_TON") (pintype "bidirectional"))
    )
    (net (code "47") (name "Net-(RGB1-PadP$1)") (class "Default")
      (node (ref "RGB1") (pin "P$1") (pinfunction "P$1_P$1") (pintype "bidirectional"))
      (node (ref "RGB2") (pin "P$6") (pinfunction "P$6_P$6") (pintype "bidirectional"))
    )
    (net (code "48") (name "Net-(RGB1-PadP$2)") (class "Default")
      (node (ref "RGB1") (pin "P$2") (pinfunction "P$2_P$2") (pintype "bidirectional"))
      (node (ref "RGB2") (pin "P$5") (pinfunction "P$5_P$5") (pintype "bidirectional"))
    )
    (net (code "49") (name "Net-(RGB1-PadP$3)") (class "Default")
      (node (ref "RGB1") (pin "P$3") (pinfunction "P$3_P$3") (pintype "bidirectional"))
      (node (ref "RGB2") (pin "P$4") (pinfunction "P$4_P$4") (pintype "bidirectional"))
    )
    (net (code "50") (name "Net-(RGB2-PadP$1)") (class "Default")
      (node (ref "RGB2") (pin "P$1") (pinfunction "P$1_P$1") (pintype "bidirectional"))
      (node (ref "RGB3") (pin "P$6") (pinfunction "P$6_P$6") (pintype "bidirectional"))
    )
    (net (code "51") (name "Net-(RGB2-PadP$2)") (class "Default")
      (node (ref "RGB2") (pin "P$2") (pinfunction "P$2_P$2") (pintype "bidirectional"))
      (node (ref "RGB3") (pin "P$5") (pinfunction "P$5_P$5") (pintype "bidirectional"))
    )
    (net (code "52") (name "Net-(RGB2-PadP$3)") (class "Default")
      (node (ref "RGB2") (pin "P$3") (pinfunction "P$3_P$3") (pintype "bidirectional"))
      (node (ref "RGB3") (pin "P$4") (pinfunction "P$4_P$4") (pintype "bidirectional"))
    )
    (net (code "53") (name "Net-(RGB4-PadP$1)") (class "Default")
      (node (ref "RGB4") (pin "P$1") (pinfunction "P$1_P$1") (pintype "bidirectional"))
      (node (ref "RGB5") (pin "P$6") (pinfunction "P$6_P$6") (pintype "bidirectional"))
    )
    (net (code "54") (name "Net-(RGB4-PadP$2)") (class "Default")
      (node (ref "RGB4") (pin "P$2") (pinfunction "P$2_P$2") (pintype "bidirectional"))
      (node (ref "RGB5") (pin "P$5") (pinfunction "P$5_P$5") (pintype "bidirectional"))
    )
    (net (code "55") (name "Net-(RGB4-PadP$3)") (class "Default")
      (node (ref "RGB4") (pin "P$3") (pinfunction "P$3_P$3") (pintype "bidirectional"))
      (node (ref "RGB5") (pin "P$4") (pinfunction "P$4_P$4") (pintype "bidirectional"))
    )
    (net (code "56") (name "Net-(RGB5-PadP$1)") (class "Default")
      (node (ref "RGB5") (pin "P$1") (pinfunction "P$1_P$1") (pintype "bidirectional"))
      (node (ref "RGB6") (pin "P$6") (pinfunction "P$6_P$6") (pintype "bidirectional"))
    )
    (net (code "57") (name "Net-(RGB5-PadP$2)") (class "Default")
      (node (ref "RGB5") (pin "P$2") (pinfunction "P$2_P$2") (pintype "bidirectional"))
      (node (ref "RGB6") (pin "P$5") (pinfunction "P$5_P$5") (pintype "bidirectional"))
    )
    (net (code "58") (name "Net-(RGB5-PadP$3)") (class "Default")
      (node (ref "RGB5") (pin "P$3") (pinfunction "P$3_P$3") (pintype "bidirectional"))
      (node (ref "RGB6") (pin "P$4") (pinfunction "P$4_P$4") (pintype "bidirectional"))
    )
    (net (code "59") (name "Net-(RN2B-2)") (class "Default")
      (node (ref "RN2") (pin "7") (pinfunction "2_7") (pintype "passive"))
      (node (ref "TX") (pin "C") (pinfunction "C_C") (pintype "passive"))
    )
    (net (code "60") (name "Net-(RN2C-2)") (class "Default")
      (node (ref "RN2") (pin "6") (pinfunction "2_6") (pintype "passive"))
      (node (ref "RX") (pin "C") (pinfunction "C_C") (pintype "passive"))
    )
    (net (code "61") (name "Net-(RN2D-2)") (class "Default")
      (node (ref "ON") (pin "C") (pinfunction "C_C") (pintype "passive"))
      (node (ref "RN2") (pin "5") (pinfunction "2_5") (pintype "passive"))
    )
    (net (code "62") (name "PWRIN") (class "Default")
      (node (ref "D1") (pin "A") (pinfunction "A_A") (pintype "passive"))
      (node (ref "PWR_EXP") (pin "2") (pinfunction "2_2") (pintype "passive"))
      (node (ref "PWR_JACK") (pin "P$1") (pinfunction "P$1_P$1") (pintype "bidirectional"))
    )
    (net (code "63") (name "RD+") (class "Default")
      (node (ref "RN3") (pin "1") (pinfunction "1_1") (pintype "passive"))
      (node (ref "U1") (pin "4") (pinfunction "D+_4") (pintype "bidirectional"))
      (node (ref "U2") (pin "4") (pinfunction "D+_4") (pintype "bidirectional"))
    )
    (net (code "64") (name "RD-") (class "Default")
      (node (ref "RN3") (pin "4") (pinfunction "1_4") (pintype "passive"))
      (node (ref "U1") (pin "3") (pinfunction "D-_3") (pintype "bidirectional"))
      (node (ref "U2") (pin "3") (pinfunction "D-_3") (pintype "bidirectional"))
    )
    (net (code "65") (name "RESET") (class "Default")
      (node (ref "D2") (pin "A") (pinfunction "A_A") (pintype "passive"))
      (node (ref "ICSP") (pin "5") (pinfunction "5_5") (pintype "passive"))
      (node (ref "JP3") (pin "3") (pinfunction "3_3") (pintype "passive"))
      (node (ref "RN1") (pin "4") (pinfunction "1_4") (pintype "passive"))
      (node (ref "RST") (pin "D") (pinfunction "D_D") (pintype "bidirectional"))
      (node (ref "RST") (pin "H") (pinfunction "H_H") (pintype "bidirectional"))
      (node (ref "RST1") (pin "D") (pinfunction "D_D") (pintype "bidirectional"))
      (node (ref "RST1") (pin "H") (pinfunction "H_H") (pintype "bidirectional"))
      (node (ref "U1") (pin "13") (pinfunction "RESET_13") (pintype "input"))
      (node (ref "U2") (pin "13") (pinfunction "RESET_13") (pintype "input"))
    )
    (net (code "66") (name "RLED") (class "Default")
      (node (ref "LED_EXP") (pin "3") (pinfunction "3_3") (pintype "passive"))
      (node (ref "R4") (pin "1") (pinfunction "1_1") (pintype "passive"))
      (node (ref "R7") (pin "1") (pinfunction "1_1") (pintype "passive"))
      (node (ref "TRED") (pin "P$2") (pinfunction "P$2_P$2") (pintype "bidirectional"))
    )
    (net (code "67") (name "RXLED") (class "Default")
      (node (ref "RN2") (pin "3") (pinfunction "1_3") (pintype "passive"))
      (node (ref "U1") (pin "8") (pinfunction "(SS/PCINT0)PB0_8") (pintype "bidirectional"))
      (node (ref "U2") (pin "8") (pinfunction "(SS/PCINT0)PB0_8") (pintype "bidirectional"))
    )
    (net (code "68") (name "SCK") (class "Default")
      (node (ref "ICSP") (pin "3") (pinfunction "3_3") (pintype "passive"))
      (node (ref "U1") (pin "9") (pinfunction "(SCLK/PCINT1)PB1_9") (pintype "bidirectional"))
      (node (ref "U2") (pin "9") (pinfunction "(SCLK/PCINT1)PB1_9") (pintype "bidirectional"))
    )
    (net (code "69") (name "SQUISH") (class "Default")
      (node (ref "IR_CONNECT") (pin "P$2") (pinfunction "PIN2_P$2") (pintype "bidirectional"))
      (node (ref "JP4") (pin "6") (pinfunction "6_6") (pintype "passive"))
      (node (ref "U1") (pin "36") (pinfunction "(ADC7/TDI)PF7_36") (pintype "bidirectional"))
      (node (ref "U2") (pin "36") (pinfunction "(ADC7/TDI)PF7_36") (pintype "bidirectional"))
    )
    (net (code "70") (name "TXLED") (class "Default")
      (node (ref "RN2") (pin "2") (pinfunction "1_2") (pintype "passive"))
      (node (ref "U1") (pin "22") (pinfunction "(XCK1/#CTS)PD5_22") (pintype "bidirectional"))
      (node (ref "U2") (pin "22") (pinfunction "(XCK1/#CTS)PD5_22") (pintype "bidirectional"))
    )
    (net (code "71") (name "UCAP") (class "Default")
      (node (ref "C7") (pin "1") (pinfunction "1_1") (pintype "passive"))
      (node (ref "U1") (pin "6") (pinfunction "UCAP_6") (pintype "passive"))
      (node (ref "U2") (pin "6") (pinfunction "UCAP_6") (pintype "passive"))
    )
    (net (code "72") (name "UGND") (class "Default")
      (node (ref "C7") (pin "2") (pinfunction "2_2") (pintype "passive"))
      (node (ref "J1") (pin "P$5") (pinfunction "GND_P$5") (pintype "bidirectional"))
      (node (ref "L2") (pin "2") (pinfunction "2_2") (pintype "passive"))
      (node (ref "R11") (pin "2") (pinfunction "2_2") (pintype "passive"))
      (node (ref "U1") (pin "5") (pinfunction "UGND_5") (pintype "power_in"))
      (node (ref "U2") (pin "5") (pinfunction "UGND_5") (pintype "power_in"))
    )
    (net (code "73") (name "USBID") (class "Default")
      (node (ref "J1") (pin "P$4") (pinfunction "ID_P$4") (pintype "bidirectional"))
    )
    (net (code "74") (name "VIN") (class "Default")
      (node (ref "C10") (pin "1") (pinfunction "1_1") (pintype "passive"))
      (node (ref "CP1") (pin "+") (pinfunction "+_+") (pintype "passive"))
      (node (ref "D1") (pin "C") (pinfunction "C_C") (pintype "passive"))
      (node (ref "IC1") (pin "3") (pinfunction "IN_3") (pintype "input"))
      (node (ref "JP3") (pin "8") (pinfunction "8_8") (pintype "passive"))
      (node (ref "LED_EXP") (pin "1") (pinfunction "1_1") (pintype "passive"))
      (node (ref "R8") (pin "2") (pinfunction "2_2") (pintype "passive"))
      (node (ref "RGB1") (pin "P$4") (pinfunction "P$4_P$4") (pintype "bidirectional"))
      (node (ref "RGB1") (pin "P$5") (pinfunction "P$5_P$5") (pintype "bidirectional"))
      (node (ref "RGB1") (pin "P$6") (pinfunction "P$6_P$6") (pintype "bidirectional"))
      (node (ref "RGB4") (pin "P$4") (pinfunction "P$4_P$4") (pintype "bidirectional"))
      (node (ref "RGB4") (pin "P$5") (pinfunction "P$5_P$5") (pintype "bidirectional"))
      (node (ref "RGB4") (pin "P$6") (pinfunction "P$6_P$6") (pintype "bidirectional"))
      (node (ref "RN1") (pin "8") (pinfunction "2_8") (pintype "passive"))
      (node (ref "U4") (pin "VIN") (pinfunction "VIN_VIN") (pintype "bidirectional"))
    )
    (net (code "75") (name "VUSB") (class "Default")
      (node (ref "C8") (pin "+") (pinfunction "+_+") (pintype "passive"))
      (node (ref "C9") (pin "1") (pinfunction "1_1") (pintype "passive"))
      (node (ref "F1") (pin "1") (pinfunction "1_1") (pintype "passive"))
      (node (ref "T1") (pin "1") (pinfunction "D_1") (pintype "passive"))
      (node (ref "U1") (pin "7") (pinfunction "VBUS_7") (pintype "input"))
      (node (ref "U2") (pin "7") (pinfunction "VBUS_7") (pintype "input"))
    )
    (net (code "76") (name "XTAL1") (class "Default")
      (node (ref "C4") (pin "2") (pinfunction "2_2") (pintype "passive"))
      (node (ref "R1") (pin "1") (pinfunction "1_1") (pintype "passive"))
      (node (ref "U1") (pin "17") (pinfunction "XTAL1_17") (pintype "bidirectional"))
      (node (ref "U2") (pin "17") (pinfunction "XTAL1_17") (pintype "bidirectional"))
      (node (ref "X1") (pin "1") (pinfunction "1_1") (pintype "passive"))
      (node (ref "X1") (pin "P$1") (pinfunction "1_P$1") (pintype "passive"))
    )
    (net (code "77") (name "XTAL2") (class "Default")
      (node (ref "C3") (pin "2") (pinfunction "2_2") (pintype "passive"))
      (node (ref "R1") (pin "2") (pinfunction "2_2") (pintype "passive"))
      (node (ref "U1") (pin "16") (pinfunction "XTAL2_16") (pintype "bidirectional"))
      (node (ref "U2") (pin "16") (pinfunction "XTAL2_16") (pintype "bidirectional"))
      (node (ref "X1") (pin "2") (pinfunction "2_2") (pintype "passive"))
      (node (ref "X1") (pin "P$2") (pinfunction "2_P$2") (pintype "passive"))
    )
    (net (code "78") (name "unconnected-(JP3-Pad1)") (class "Default")
      (node (ref "JP3") (pin "1") (pinfunction "1_1") (pintype "passive"))
    )
    (net (code "79") (name "unconnected-(RN3B-1-Pad2)") (class "Default")
      (node (ref "RN3") (pin "2") (pinfunction "1_2") (pintype "passive"))
    )
    (net (code "80") (name "unconnected-(RN3B-2-Pad7)") (class "Default")
      (node (ref "RN3") (pin "7") (pinfunction "2_7") (pintype "passive"))
    )
    (net (code "81") (name "unconnected-(RN3C-1-Pad3)") (class "Default")
      (node (ref "RN3") (pin "3") (pinfunction "1_3") (pintype "passive"))
    )
    (net (code "82") (name "unconnected-(RN3C-2-Pad6)") (class "Default")
      (node (ref "RN3") (pin "6") (pinfunction "2_6") (pintype "passive"))
    )
    (net (code "83") (name "unconnected-(U3-NC{slash}FB-Pad4)") (class "Default")
      (node (ref "U3") (pin "4") (pinfunction "NC/FB_4") (pintype "passive"))
    )
  )
)
